# harp_expander_servo_driver_v1_0.net
KiCad netlist of a schematic drawn in EAGLE
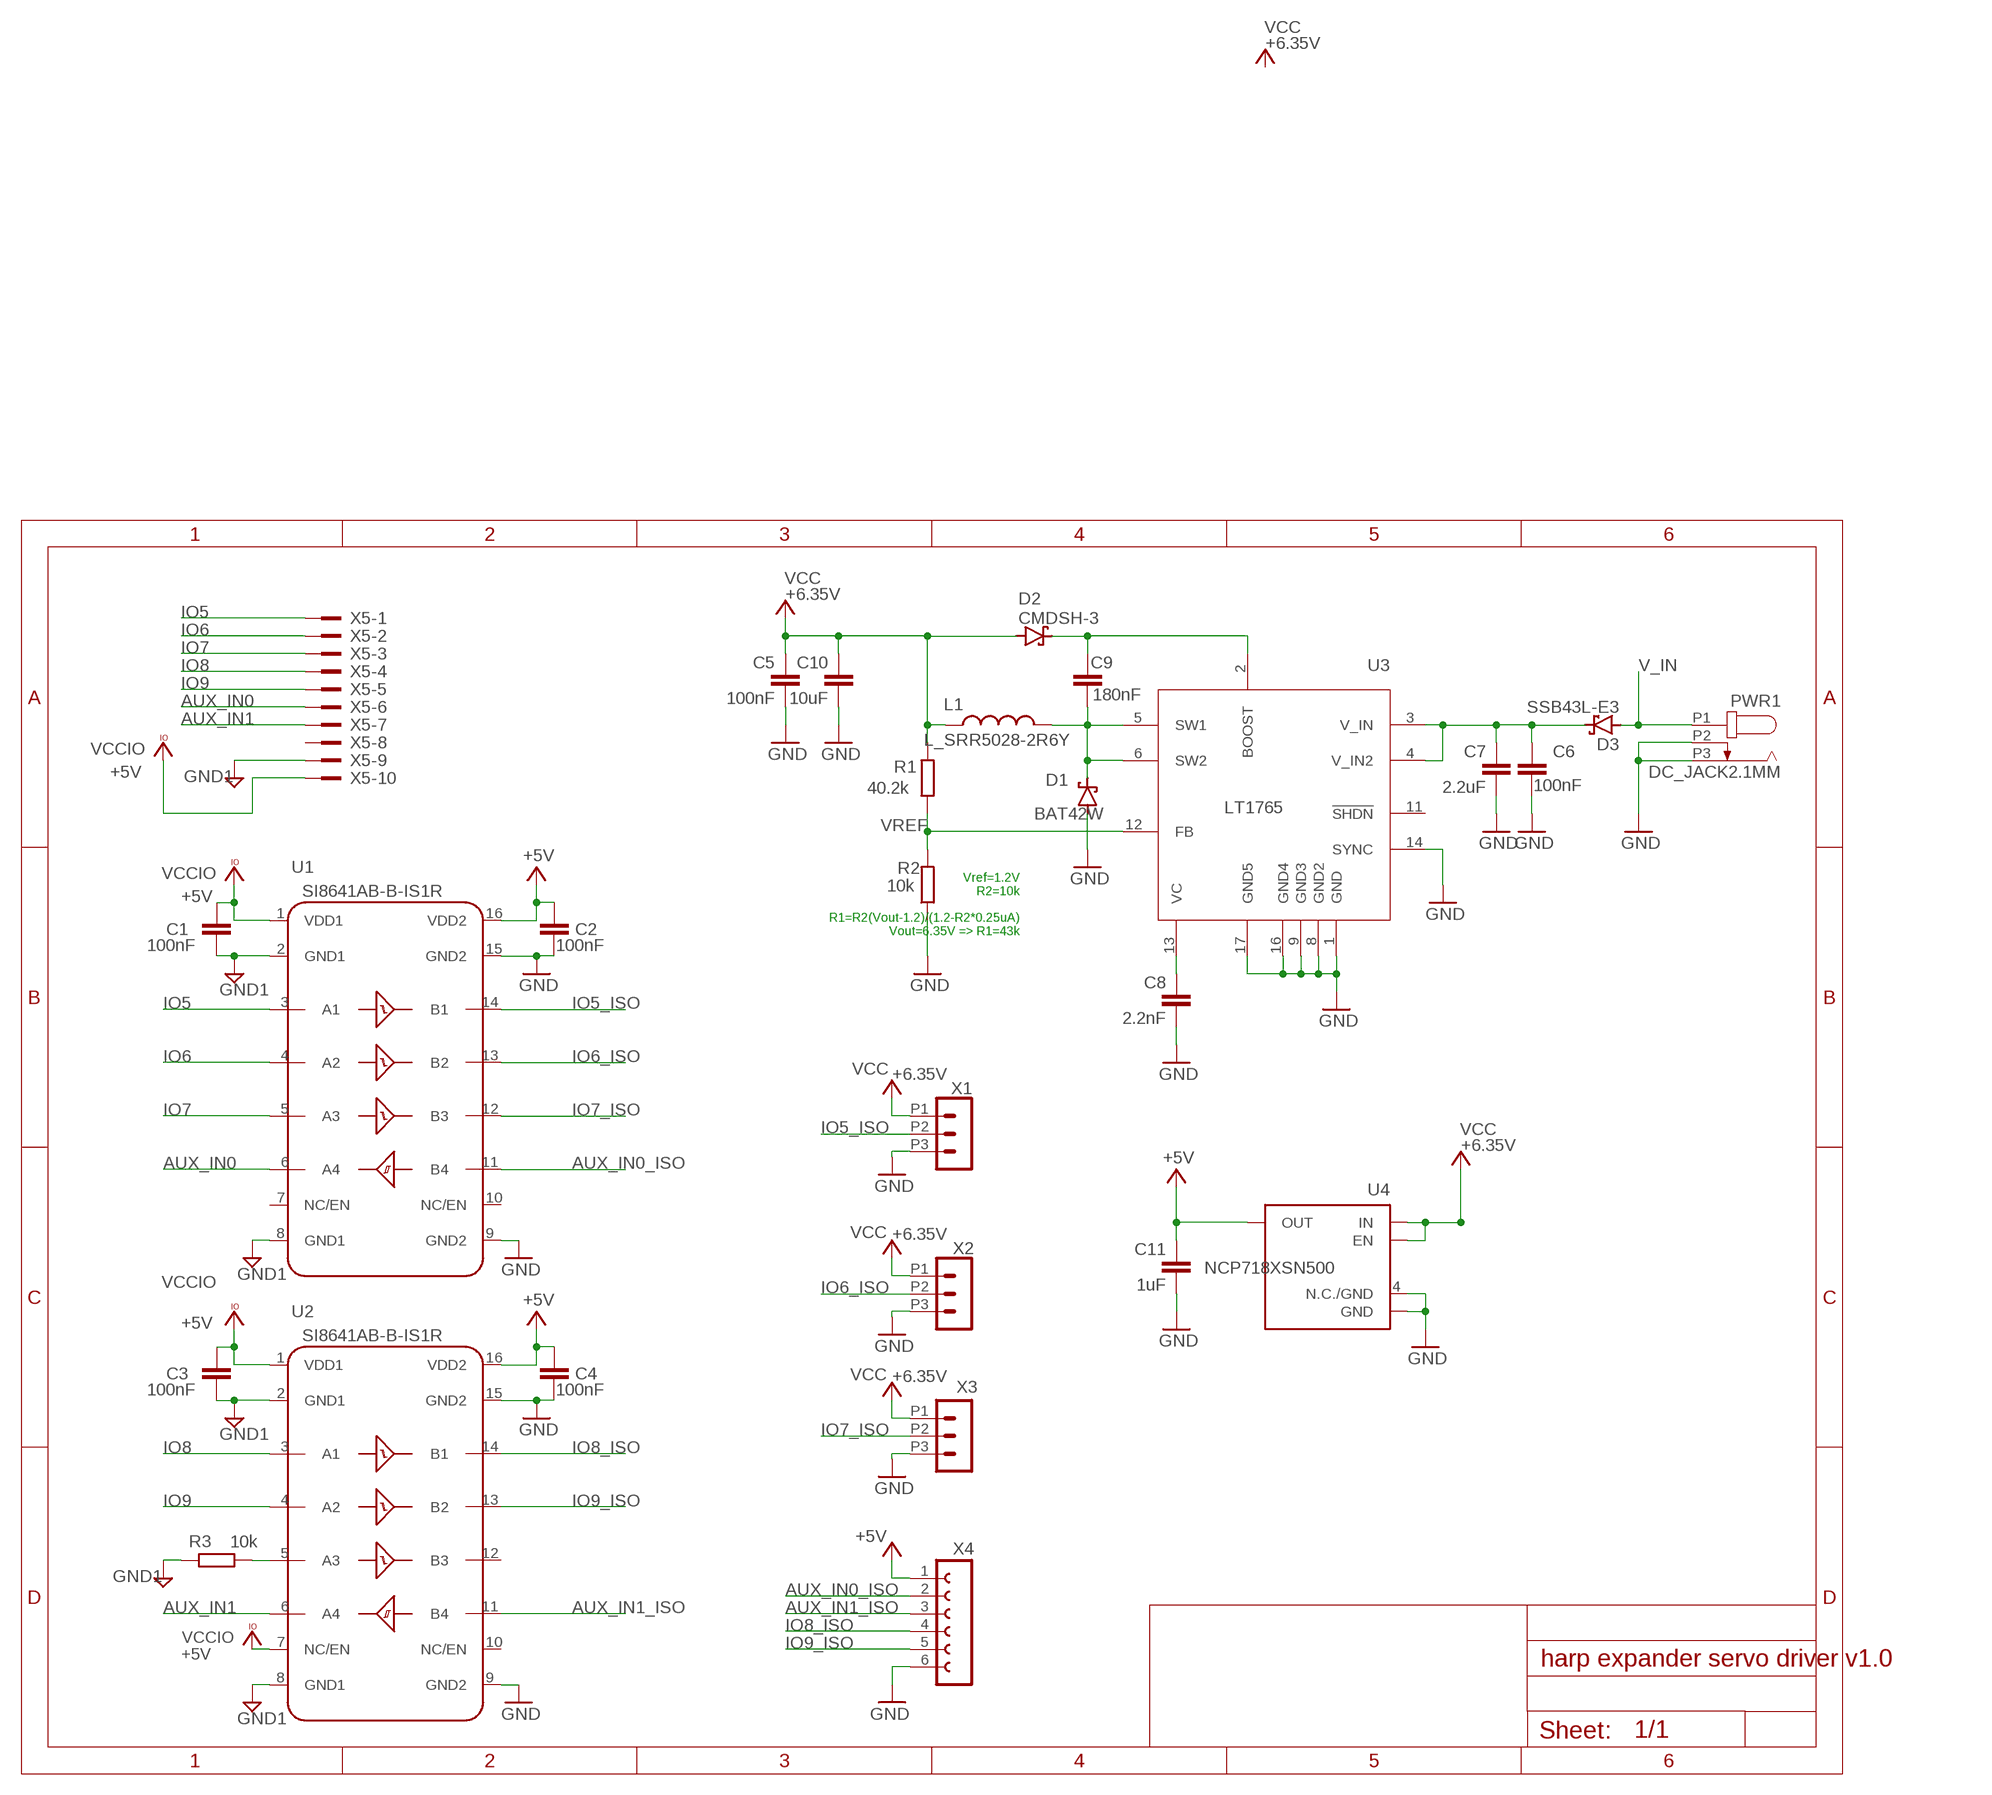
[diagram p0: schematic, sheet 1]

(export (version "E")
  (design (tool "Eeschema 10.0.6"))
  (components
    (comp (ref "C1")
      (value "100nF")
      (footprint "eagle-import:C0402")
      (fields (field (name "MPN") "CGA2B3X7R1H104K050BB"))
      (libsource (lib "eagle-import") (part "C-EUC0402"))
    )
    (comp (ref "C2")
      (value "100nF")
      (footprint "eagle-import:C0402")
      (fields (field (name "MPN") "CGA2B3X7R1H104K050BB"))
      (libsource (lib "eagle-import") (part "C-EUC0402"))
    )
    (comp (ref "C3")
      (value "100nF")
      (footprint "eagle-import:C0402")
      (fields (field (name "MPN") "CGA2B3X7R1H104K050BB"))
      (libsource (lib "eagle-import") (part "C-EUC0402"))
    )
    (comp (ref "C4")
      (value "100nF")
      (footprint "eagle-import:C0402")
      (fields (field (name "MPN") "CGA2B3X7R1H104K050BB"))
      (libsource (lib "eagle-import") (part "C-EUC0402"))
    )
    (comp (ref "C5")
      (value "100nF")
      (footprint "eagle-import:C0402")
      (fields (field (name "MPN") "CGA2B3X7R1H104K050BB"))
      (libsource (lib "eagle-import") (part "C-EUC0402"))
    )
    (comp (ref "C6")
      (value "100nF")
      (footprint "eagle-import:C0402")
      (fields (field (name "MPN") "CGA2B3X7R1H104K050BB"))
      (libsource (lib "eagle-import") (part "C-EUC0402"))
    )
    (comp (ref "C7")
      (value "2.2uF")
      (footprint "eagle-import:C0603")
      (fields (field (name "MPN") "GRM188R61E225MA12D"))
      (libsource (lib "eagle-import") (part "C-EUC0603"))
    )
    (comp (ref "C8")
      (value "2.2nF")
      (footprint "eagle-import:C0402")
      (fields (field (name "MPN") "CL05B222JB5NNNC"))
      (libsource (lib "eagle-import") (part "C-EUC0402"))
    )
    (comp (ref "C9")
      (value "180nF")
      (footprint "eagle-import:C0603")
      (fields (field (name "MPN") "GCG188R91H184KA01D"))
      (libsource (lib "eagle-import") (part "C-EUC0603"))
    )
    (comp (ref "C10")
      (value "10uF")
      (footprint "eagle-import:C0603")
      (fields (field (name "MPN") "EMK107BBJ106MA-T"))
      (libsource (lib "eagle-import") (part "C-EUC0603"))
    )
    (comp (ref "C11")
      (value "1uF")
      (footprint "eagle-import:C0603")
      (fields (field (name "MPN") "CL10B105KA8NNNC"))
      (libsource (lib "eagle-import") (part "C-EUC0603"))
    )
    (comp (ref "D1")
      (value "BAT42W")
      (footprint "eagle-import:POWERMITE")
      (fields (field (name "MPN") "BAT42W-E3-08"))
      (libsource (lib "eagle-import") (part "SCHOTTKY-DIODECASE457"))
    )
    (comp (ref "D2")
      (value "CMDSH-3")
      (footprint "eagle-import:SOD323-R")
      (libsource (lib "eagle-import") (part "SCHOTTKY-DIODESOD323"))
    )
    (comp (ref "D3")
      (value "SSB43L-E3")
      (footprint "eagle-import:SMB")
      (fields (field (name "MPN") "SSB43L-E3/52T"))
      (libsource (lib "eagle-import") (part "MBRS130LT3"))
    )
    (comp (ref "L1")
      (value "L_SRR5028-2R6Y")
      (footprint "eagle-import:COILCRAFT_1")
      (fields (field (name "MPN") "SRR5028-2R6Y"))
      (libsource (lib "eagle-import") (part "L_SRR5028-2R6Y"))
    )
    (comp (ref "PWR1")
      (value "DC_JACK2.1MM")
      (footprint "eagle-import:DC_POWER_INPUT_2.1MM")
      (fields (field (name "MPN") "163-179PH-EX"))
      (libsource (lib "eagle-import") (part "DC_JACK2.1MM"))
    )
    (comp (ref "R1")
      (value "40.2k")
      (footprint "eagle-import:R0402")
      (fields (field (name "MPN") "RC0402FR-0740K2L"))
      (libsource (lib "eagle-import") (part "R-EU_R0402"))
    )
    (comp (ref "R2")
      (value "10k")
      (footprint "eagle-import:R0402")
      (fields (field (name "MPN") "CRCW040210K0FKEDC"))
      (libsource (lib "eagle-import") (part "R-EU_R0402"))
    )
    (comp (ref "R3")
      (value "10k")
      (footprint "eagle-import:R0402")
      (fields (field (name "MPN") "CRCW040210K0FKEDC"))
      (libsource (lib "eagle-import") (part "R-EU_R0402"))
    )
    (comp (ref "U1")
      (value "SI8641AB-B-IS1R")
      (footprint "eagle-import:SO16W")
      (libsource (lib "eagle-import") (part "SI8641ABW"))
    )
    (comp (ref "U2")
      (value "SI8641AB-B-IS1R")
      (footprint "eagle-import:SO16W")
      (libsource (lib "eagle-import") (part "SI8641ABW"))
    )
    (comp (ref "U3")
      (value "LT1765")
      (footprint "eagle-import:TSSOP16")
      (description "Buck Switching Regulator Output 3A")
      (fields (field (name "MPN") "LT1765EFE#TRPBF"))
      (libsource (lib "eagle-import") (part "LT1765"))
    )
    (comp (ref "U4")
      (value "NCP718XSN500")
      (footprint "eagle-import:SOT23-5")
      (fields (field (name "MPN") "NCP718BSN500T1G"))
      (libsource (lib "eagle-import") (part "NCP718XSN500"))
    )
    (comp (ref "X1")
      (value "CON_3.5MM_1X3")
      (footprint "eagle-import:CON_3.5MM_1X3")
      (fields (field (name "MPN") "691322110003"))
      (libsource (lib "eagle-import") (part "CON_3.5MM_1X3"))
    )
    (comp (ref "X2")
      (value "CON_3.5MM_1X3")
      (footprint "eagle-import:CON_3.5MM_1X3")
      (fields (field (name "MPN") "691322110003"))
      (libsource (lib "eagle-import") (part "CON_3.5MM_1X3"))
    )
    (comp (ref "X3")
      (value "CON_3.5MM_1X3")
      (footprint "eagle-import:CON_3.5MM_1X3")
      (fields (field (name "MPN") "691322110003"))
      (libsource (lib "eagle-import") (part "CON_3.5MM_1X3"))
    )
    (comp (ref "X4")
      (value "aux_header")
      (footprint "eagle-import:FE06")
      (fields (field (name "MPN") "n.a."))
      (libsource (lib "eagle-import") (part "FE06-1"))
    )
    (comp (ref "X5")
      (value "2510-")
      (footprint "eagle-import:PAK100_2500-10")
      (fields
        (field (name "MF") "3M")
        (field (name "MPN") "2510-6002UB")
        (field (name "DIGIKEY_PN") "S9169-ND")
        (field (name "MF_1") "-")
        (field (name "MPN_1") "SBH11-PBPC-D05-ST-BK")
        (field (name "OC_FARNELL") "-")
        (field (name "OC_NEWARK") "-")
      )
      (libsource (lib "eagle-import") (part "2510-"))
    )
  )
  (nets
    (net (code "1") (name "+5V") (class "Default")
      (node (ref "C11") (pin "1") (pinfunction "1_1") (pintype "passive"))
      (node (ref "C2") (pin "1") (pinfunction "1_1") (pintype "passive"))
      (node (ref "C4") (pin "1") (pinfunction "1_1") (pintype "passive"))
      (node (ref "U1") (pin "16") (pinfunction "VDD2_16") (pintype "bidirectional"))
      (node (ref "U2") (pin "16") (pinfunction "VDD2_16") (pintype "bidirectional"))
      (node (ref "U4") (pin "5") (pinfunction "OUT_5") (pintype "passive"))
      (node (ref "X4") (pin "1") (pinfunction "1_1") (pintype "passive"))
    )
    (net (code "2") (name "/AUX_IN0") (class "Default")
      (node (ref "U1") (pin "6") (pinfunction "A4_6") (pintype "bidirectional"))
      (node (ref "X5") (pin "6") (pinfunction "KL_6") (pintype "passive"))
    )
    (net (code "3") (name "/AUX_IN0_ISO") (class "Default")
      (node (ref "U1") (pin "11") (pinfunction "B4_11") (pintype "bidirectional"))
      (node (ref "X4") (pin "2") (pinfunction "2_2") (pintype "passive"))
    )
    (net (code "4") (name "/AUX_IN1") (class "Default")
      (node (ref "U2") (pin "6") (pinfunction "A4_6") (pintype "bidirectional"))
      (node (ref "X5") (pin "7") (pinfunction "KL_7") (pintype "passive"))
    )
    (net (code "5") (name "/AUX_IN1_ISO") (class "Default")
      (node (ref "U2") (pin "11") (pinfunction "B4_11") (pintype "bidirectional"))
      (node (ref "X4") (pin "3") (pinfunction "3_3") (pintype "passive"))
    )
    (net (code "6") (name "/IO5") (class "Default")
      (node (ref "U1") (pin "3") (pinfunction "A1_3") (pintype "bidirectional"))
      (node (ref "X5") (pin "1") (pinfunction "KL_1") (pintype "passive"))
    )
    (net (code "7") (name "/IO5_ISO") (class "Default")
      (node (ref "U1") (pin "14") (pinfunction "B1_14") (pintype "bidirectional"))
      (node (ref "X1") (pin "P2") (pinfunction "2_P2") (pintype "passive"))
    )
    (net (code "8") (name "/IO6") (class "Default")
      (node (ref "U1") (pin "4") (pinfunction "A2_4") (pintype "bidirectional"))
      (node (ref "X5") (pin "2") (pinfunction "KL_2") (pintype "passive"))
    )
    (net (code "9") (name "/IO6_ISO") (class "Default")
      (node (ref "U1") (pin "13") (pinfunction "B2_13") (pintype "bidirectional"))
      (node (ref "X2") (pin "P2") (pinfunction "2_P2") (pintype "passive"))
    )
    (net (code "10") (name "/IO7") (class "Default")
      (node (ref "U1") (pin "5") (pinfunction "A3_5") (pintype "bidirectional"))
      (node (ref "X5") (pin "3") (pinfunction "KL_3") (pintype "passive"))
    )
    (net (code "11") (name "/IO7_ISO") (class "Default")
      (node (ref "U1") (pin "12") (pinfunction "B3_12") (pintype "bidirectional"))
      (node (ref "X3") (pin "P2") (pinfunction "2_P2") (pintype "passive"))
    )
    (net (code "12") (name "/IO8") (class "Default")
      (node (ref "U2") (pin "3") (pinfunction "A1_3") (pintype "bidirectional"))
      (node (ref "X5") (pin "4") (pinfunction "KL_4") (pintype "passive"))
    )
    (net (code "13") (name "/IO8_ISO") (class "Default")
      (node (ref "U2") (pin "14") (pinfunction "B1_14") (pintype "bidirectional"))
      (node (ref "X4") (pin "4") (pinfunction "4_4") (pintype "passive"))
    )
    (net (code "14") (name "/IO9") (class "Default")
      (node (ref "U2") (pin "4") (pinfunction "A2_4") (pintype "bidirectional"))
      (node (ref "X5") (pin "5") (pinfunction "KL_5") (pintype "passive"))
    )
    (net (code "15") (name "/IO9_ISO") (class "Default")
      (node (ref "U2") (pin "13") (pinfunction "B2_13") (pintype "bidirectional"))
      (node (ref "X4") (pin "5") (pinfunction "5_5") (pintype "passive"))
    )
    (net (code "16") (name "/VREF") (class "Default")
      (node (ref "R1") (pin "1") (pinfunction "1_1") (pintype "passive"))
      (node (ref "R2") (pin "2") (pinfunction "2_2") (pintype "passive"))
      (node (ref "U3") (pin "12") (pinfunction "FB_12") (pintype "passive"))
    )
    (net (code "17") (name "/V_IN") (class "Default")
      (node (ref "D3") (pin "A") (pinfunction "A_A") (pintype "passive"))
      (node (ref "PWR1") (pin "P1") (pinfunction "1_P1") (pintype "passive"))
    )
    (net (code "18") (name "GND") (class "Default")
      (node (ref "C10") (pin "2") (pinfunction "2_2") (pintype "passive"))
      (node (ref "C11") (pin "2") (pinfunction "2_2") (pintype "passive"))
      (node (ref "C2") (pin "2") (pinfunction "2_2") (pintype "passive"))
      (node (ref "C4") (pin "2") (pinfunction "2_2") (pintype "passive"))
      (node (ref "C5") (pin "2") (pinfunction "2_2") (pintype "passive"))
      (node (ref "C6") (pin "2") (pinfunction "2_2") (pintype "passive"))
      (node (ref "C7") (pin "2") (pinfunction "2_2") (pintype "passive"))
      (node (ref "C8") (pin "2") (pinfunction "2_2") (pintype "passive"))
      (node (ref "D1") (pin "2") (pinfunction "A_2") (pintype "passive"))
      (node (ref "PWR1") (pin "P2") (pinfunction "2_P2") (pintype "passive"))
      (node (ref "PWR1") (pin "P3") (pinfunction "3_P3") (pintype "passive"))
      (node (ref "R2") (pin "1") (pinfunction "1_1") (pintype "passive"))
      (node (ref "U1") (pin "15") (pinfunction "GND2_15") (pintype "bidirectional"))
      (node (ref "U1") (pin "9") (pinfunction "GND2_9") (pintype "bidirectional"))
      (node (ref "U2") (pin "15") (pinfunction "GND2_15") (pintype "bidirectional"))
      (node (ref "U2") (pin "9") (pinfunction "GND2_9") (pintype "bidirectional"))
      (node (ref "U3") (pin "1") (pinfunction "GND_1") (pintype "passive"))
      (node (ref "U3") (pin "14") (pinfunction "SYNC_14") (pintype "passive"))
      (node (ref "U3") (pin "16") (pinfunction "GND4_16") (pintype "passive"))
      (node (ref "U3") (pin "17") (pinfunction "GND5_17") (pintype "passive"))
      (node (ref "U3") (pin "8") (pinfunction "GND2_8") (pintype "passive"))
      (node (ref "U3") (pin "9") (pinfunction "GND3_9") (pintype "passive"))
      (node (ref "U4") (pin "2") (pinfunction "GND_2") (pintype "passive"))
      (node (ref "U4") (pin "4") (pinfunction "N.C./GND_4") (pintype "passive"))
      (node (ref "X1") (pin "P3") (pinfunction "3_P3") (pintype "passive"))
      (node (ref "X2") (pin "P3") (pinfunction "3_P3") (pintype "passive"))
      (node (ref "X3") (pin "P3") (pinfunction "3_P3") (pintype "passive"))
      (node (ref "X4") (pin "6") (pinfunction "6_6") (pintype "passive"))
    )
    (net (code "19") (name "GND1") (class "Default")
      (node (ref "C1") (pin "2") (pinfunction "2_2") (pintype "passive"))
      (node (ref "C3") (pin "2") (pinfunction "2_2") (pintype "passive"))
      (node (ref "R3") (pin "2") (pinfunction "2_2") (pintype "passive"))
      (node (ref "U1") (pin "2") (pinfunction "GND1_2") (pintype "bidirectional"))
      (node (ref "U1") (pin "8") (pinfunction "GND1_8") (pintype "bidirectional"))
      (node (ref "U2") (pin "2") (pinfunction "GND1_2") (pintype "bidirectional"))
      (node (ref "U2") (pin "8") (pinfunction "GND1_8") (pintype "bidirectional"))
      (node (ref "X5") (pin "9") (pinfunction "KL_9") (pintype "passive"))
    )
    (net (code "20") (name "Net-(D1-C)") (class "Default")
      (node (ref "C9") (pin "2") (pinfunction "2_2") (pintype "passive"))
      (node (ref "D1") (pin "1") (pinfunction "C_1") (pintype "passive"))
      (node (ref "L1") (pin "2") (pinfunction "2_2") (pintype "passive"))
      (node (ref "U3") (pin "5") (pinfunction "SW1_5") (pintype "passive"))
      (node (ref "U3") (pin "6") (pinfunction "SW2_6") (pintype "passive"))
    )
    (net (code "21") (name "Net-(U2-A3)") (class "Default")
      (node (ref "R3") (pin "1") (pinfunction "1_1") (pintype "passive"))
      (node (ref "U2") (pin "5") (pinfunction "A3_5") (pintype "bidirectional"))
    )
    (net (code "22") (name "Net-(U3-BOOST)") (class "Default")
      (node (ref "C9") (pin "1") (pinfunction "1_1") (pintype "passive"))
      (node (ref "D2") (pin "C") (pinfunction "C_C") (pintype "passive"))
      (node (ref "U3") (pin "2") (pinfunction "BOOST_2") (pintype "passive"))
    )
    (net (code "23") (name "Net-(U3-VC)") (class "Default")
      (node (ref "C8") (pin "1") (pinfunction "1_1") (pintype "passive"))
      (node (ref "U3") (pin "13") (pinfunction "VC_13") (pintype "passive"))
    )
    (net (code "24") (name "Net-(U3-V_IN)") (class "Default")
      (node (ref "C6") (pin "1") (pinfunction "1_1") (pintype "passive"))
      (node (ref "C7") (pin "1") (pinfunction "1_1") (pintype "passive"))
      (node (ref "D3") (pin "C") (pinfunction "C_C") (pintype "passive"))
      (node (ref "U3") (pin "3") (pinfunction "V_IN_3") (pintype "passive"))
      (node (ref "U3") (pin "4") (pinfunction "V_IN2_4") (pintype "passive"))
    )
    (net (code "25") (name "VCC") (class "Default")
      (node (ref "C10") (pin "1") (pinfunction "1_1") (pintype "passive"))
      (node (ref "C5") (pin "1") (pinfunction "1_1") (pintype "passive"))
      (node (ref "D2") (pin "A") (pinfunction "A_A") (pintype "passive"))
      (node (ref "L1") (pin "1") (pinfunction "1_1") (pintype "passive"))
      (node (ref "R1") (pin "2") (pinfunction "2_2") (pintype "passive"))
      (node (ref "U4") (pin "1") (pinfunction "IN_1") (pintype "passive"))
      (node (ref "U4") (pin "3") (pinfunction "EN_3") (pintype "passive"))
      (node (ref "X1") (pin "P1") (pinfunction "1_P1") (pintype "passive"))
      (node (ref "X2") (pin "P1") (pinfunction "1_P1") (pintype "passive"))
      (node (ref "X3") (pin "P1") (pinfunction "1_P1") (pintype "passive"))
    )
    (net (code "26") (name "VCCIO") (class "Default")
      (node (ref "C1") (pin "1") (pinfunction "1_1") (pintype "passive"))
      (node (ref "C3") (pin "1") (pinfunction "1_1") (pintype "passive"))
      (node (ref "U1") (pin "1") (pinfunction "VDD1_1") (pintype "bidirectional"))
      (node (ref "U2") (pin "1") (pinfunction "VDD1_1") (pintype "bidirectional"))
      (node (ref "U2") (pin "7") (pinfunction "NC/EN_7") (pintype "bidirectional"))
      (node (ref "X5") (pin "10") (pinfunction "KL_10") (pintype "passive"))
    )
    (net (code "27") (name "unconnected-(U1-NC{slash}EN-Pad7)") (class "Default")
      (node (ref "U1") (pin "7") (pinfunction "NC/EN_7") (pintype "bidirectional"))
    )
    (net (code "28") (name "unconnected-(U1-NC{slash}EN-Pad10)") (class "Default")
      (node (ref "U1") (pin "10") (pinfunction "NC/EN_10") (pintype "bidirectional"))
    )
    (net (code "29") (name "unconnected-(U2-B3-Pad12)") (class "Default")
      (node (ref "U2") (pin "12") (pinfunction "B3_12") (pintype "bidirectional"))
    )
    (net (code "30") (name "unconnected-(U2-NC{slash}EN-Pad10)") (class "Default")
      (node (ref "U2") (pin "10") (pinfunction "NC/EN_10") (pintype "bidirectional"))
    )
    (net (code "31") (name "unconnected-(U3-NC7-Pad7)") (class "Default")
      (node (ref "U3") (pin "7") (pinfunction "NC7_7") (pintype "no_connect"))
    )
    (net (code "32") (name "unconnected-(U3-NC10-Pad10)") (class "Default")
      (node (ref "U3") (pin "10") (pinfunction "NC10_10") (pintype "no_connect"))
    )
    (net (code "33") (name "unconnected-(U3-NC15-Pad15)") (class "Default")
      (node (ref "U3") (pin "15") (pinfunction "NC15_15") (pintype "no_connect"))
    )
    (net (code "34") (name "unconnected-(U3-~{SHDN}-Pad11)") (class "Default")
      (node (ref "U3") (pin "11") (pinfunction "~{SHDN}_11") (pintype "passive"))
    )
    (net (code "35") (name "unconnected-(X5I-KL-Pad8)") (class "Default")
      (node (ref "X5") (pin "8") (pinfunction "KL_8") (pintype "passive"))
    )
  )
)
